# SensorPCB.net
KiCad netlist of a schematic drawn in EAGLE
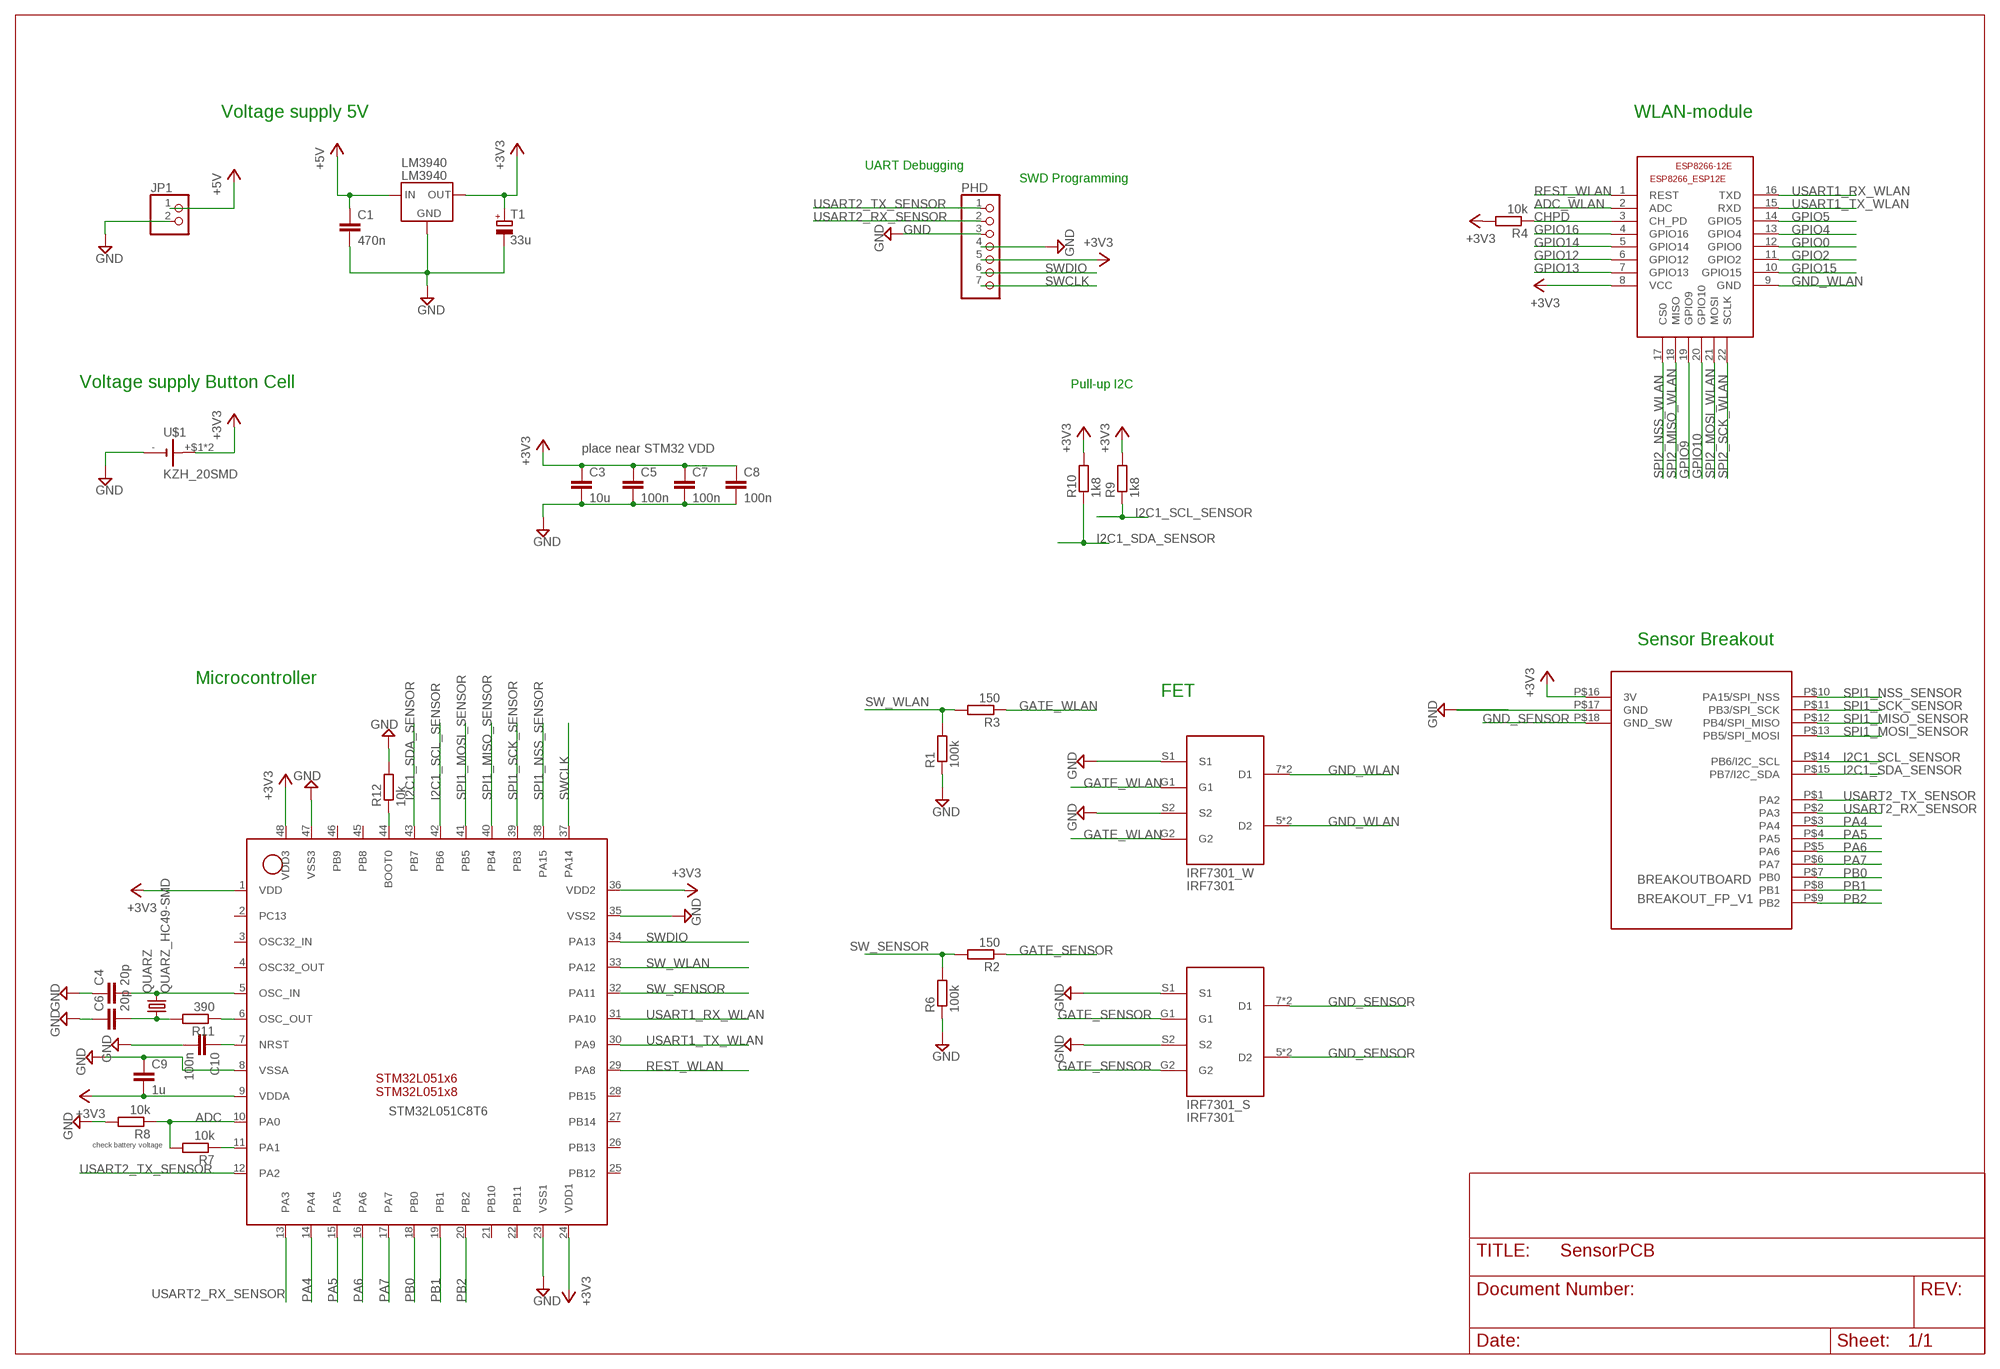
[diagram p0: schematic, sheet 1]

(export (version "E")
  (design (tool "Eeschema 10.0.6"))
  (components
    (comp (ref "BREAKOUTBOARD")
      (value "BREAKOUT_FP_V1")
      (footprint "eagle-import:BREAKOUT_FOOTPRINT_V1")
      (libsource (lib "eagle-import") (part "BREAKOUT_FP_V1"))
    )
    (comp (ref "C1")
      (value "470n")
      (footprint "eagle-import:C0805")
      (libsource (lib "eagle-import") (part "C-EUC0805"))
    )
    (comp (ref "C3")
      (value "10u")
      (footprint "eagle-import:C0805")
      (libsource (lib "eagle-import") (part "C-EUC0805"))
    )
    (comp (ref "C4")
      (value "20p")
      (footprint "eagle-import:C0805")
      (libsource (lib "eagle-import") (part "C-EUC0805"))
    )
    (comp (ref "C5")
      (value "100n")
      (footprint "eagle-import:C0805")
      (libsource (lib "eagle-import") (part "C-EUC0805"))
    )
    (comp (ref "C6")
      (value "20p")
      (footprint "eagle-import:C0805")
      (libsource (lib "eagle-import") (part "C-EUC0805"))
    )
    (comp (ref "C7")
      (value "100n")
      (footprint "eagle-import:C0805")
      (libsource (lib "eagle-import") (part "C-EUC0805"))
    )
    (comp (ref "C8")
      (value "100n")
      (footprint "eagle-import:C0805")
      (libsource (lib "eagle-import") (part "C-EUC0805"))
    )
    (comp (ref "C9")
      (value "1u")
      (footprint "eagle-import:C0805")
      (libsource (lib "eagle-import") (part "C-EUC0805"))
    )
    (comp (ref "C10")
      (value "100n")
      (footprint "eagle-import:C0805")
      (libsource (lib "eagle-import") (part "C-EUC0805"))
    )
    (comp (ref "ESP8266-12E")
      (value "ESP8266-12EESP8266-ESP12E")
      (footprint "eagle-import:ESP8266-ESP12E")
      (libsource (lib "eagle-import") (part "ESP8266-12EESP8266-ESP12E"))
    )
    (comp (ref "IRF7301_S")
      (value "IRF7301")
      (footprint "eagle-import:IRF7301_PACK_SO8")
      (libsource (lib "eagle-import") (part "IRF7301"))
    )
    (comp (ref "IRF7301_W")
      (value "IRF7301")
      (footprint "eagle-import:IRF7301_PACK_SO8")
      (libsource (lib "eagle-import") (part "IRF7301"))
    )
    (comp (ref "JP1")
      (value "PINHD-1X2_2.54-SMD")
      (footprint "eagle-import:1X02SMD")
      (libsource (lib "eagle-import") (part "PINHD-1X2_2.54-SMD"))
    )
    (comp (ref "LM3940")
      (value "LM3940")
      (footprint "eagle-import:LM3940_PACK")
      (libsource (lib "eagle-import") (part "LM3940"))
    )
    (comp (ref "PHD")
      (value "PINHD-1X7_2.54-SMD")
      (footprint "eagle-import:1X07SMD")
      (libsource (lib "eagle-import") (part "PINHD-1X7_2.54-SMD"))
    )
    (comp (ref "QUARZ")
      (value "QUARZ_HC49-SMD")
      (footprint "eagle-import:HC49-SMD")
      (libsource (lib "eagle-import") (part "QUARZ_HC49-SMD"))
    )
    (comp (ref "R1")
      (value "100k")
      (footprint "eagle-import:R0805")
      (libsource (lib "eagle-import") (part "R-EU_R0805"))
    )
    (comp (ref "R2")
      (value "150")
      (footprint "eagle-import:R0805")
      (libsource (lib "eagle-import") (part "R-EU_R0805"))
    )
    (comp (ref "R3")
      (value "150")
      (footprint "eagle-import:R0805")
      (libsource (lib "eagle-import") (part "R-EU_R0805"))
    )
    (comp (ref "R4")
      (value "10k")
      (footprint "eagle-import:R0805")
      (libsource (lib "eagle-import") (part "R-EU_R0805"))
    )
    (comp (ref "R6")
      (value "100k")
      (footprint "eagle-import:R0805")
      (libsource (lib "eagle-import") (part "R-EU_R0805"))
    )
    (comp (ref "R7")
      (value "10k")
      (footprint "eagle-import:R0805")
      (libsource (lib "eagle-import") (part "R-EU_R0805"))
    )
    (comp (ref "R8")
      (value "10k")
      (footprint "eagle-import:R0805")
      (libsource (lib "eagle-import") (part "R-EU_R0805"))
    )
    (comp (ref "R9")
      (value "1k8")
      (footprint "eagle-import:R0805")
      (libsource (lib "eagle-import") (part "R-EU_R0805"))
    )
    (comp (ref "R10")
      (value "1k8")
      (footprint "eagle-import:R0805")
      (libsource (lib "eagle-import") (part "R-EU_R0805"))
    )
    (comp (ref "R11")
      (value "390")
      (footprint "eagle-import:R0805")
      (libsource (lib "eagle-import") (part "R-EU_R0805"))
    )
    (comp (ref "R12")
      (value "10k")
      (footprint "eagle-import:R0805")
      (libsource (lib "eagle-import") (part "R-EU_R0805"))
    )
    (comp (ref "STM32L051C8T6")
      (value "STM32L051X6/8")
      (footprint "eagle-import:LQFP48")
      (libsource (lib "eagle-import") (part "STM32L051X6/8"))
    )
    (comp (ref "T1")
      (value "33u")
      (footprint "eagle-import:1206")
      (libsource (lib "eagle-import") (part "CAP_TANTAL_1206"))
    )
    (comp (ref "U$1")
      (value "KZH_20SMD")
      (footprint "eagle-import:KHZ_20SMD")
      (libsource (lib "eagle-import") (part "KZH_20SMD"))
    )
  )
  (nets
    (net (code "1") (name "+3V3") (class "Default")
      (node (ref "BREAKOUTBOARD") (pin "P$16") (pinfunction "3V_P$16") (pintype "bidirectional"))
      (node (ref "C3") (pin "1") (pinfunction "1_1") (pintype "passive"))
      (node (ref "C5") (pin "1") (pinfunction "1_1") (pintype "passive"))
      (node (ref "C7") (pin "1") (pinfunction "1_1") (pintype "passive"))
      (node (ref "C8") (pin "1") (pinfunction "1_1") (pintype "passive"))
      (node (ref "C9") (pin "2") (pinfunction "2_2") (pintype "passive"))
      (node (ref "ESP8266-12E") (pin "8") (pinfunction "VCC_8") (pintype "bidirectional"))
      (node (ref "LM3940") (pin "3") (pinfunction "OUT_3") (pintype "passive"))
      (node (ref "PHD") (pin "5") (pinfunction "5_5") (pintype "passive"))
      (node (ref "R10") (pin "2") (pinfunction "2_2") (pintype "passive"))
      (node (ref "R4") (pin "2") (pinfunction "2_2") (pintype "passive"))
      (node (ref "R9") (pin "2") (pinfunction "2_2") (pintype "passive"))
      (node (ref "STM32L051C8T6") (pin "1") (pinfunction "VDD_1") (pintype "bidirectional"))
      (node (ref "STM32L051C8T6") (pin "24") (pinfunction "VDD1_24") (pintype "bidirectional"))
      (node (ref "STM32L051C8T6") (pin "36") (pinfunction "VDD2_36") (pintype "bidirectional"))
      (node (ref "STM32L051C8T6") (pin "48") (pinfunction "VDD3_48") (pintype "bidirectional"))
      (node (ref "STM32L051C8T6") (pin "9") (pinfunction "VDDA_9") (pintype "input"))
      (node (ref "T1") (pin "1") (pinfunction "+_1") (pintype "passive"))
      (node (ref "U$1") (pin "+$1") (pinfunction "+_+$1") (pintype "passive"))
      (node (ref "U$1") (pin "+$2") (pinfunction "+_+$2") (pintype "passive"))
    )
    (net (code "2") (name "+5V") (class "Default")
      (node (ref "C1") (pin "1") (pinfunction "1_1") (pintype "passive"))
      (node (ref "JP1") (pin "1") (pinfunction "1_1") (pintype "passive"))
      (node (ref "LM3940") (pin "1") (pinfunction "IN_1") (pintype "input"))
    )
    (net (code "3") (name "/ADC") (class "Default")
      (node (ref "R7") (pin "2") (pinfunction "2_2") (pintype "passive"))
      (node (ref "R8") (pin "1") (pinfunction "1_1") (pintype "passive"))
      (node (ref "STM32L051C8T6") (pin "10") (pinfunction "PA0_10") (pintype "passive"))
    )
    (net (code "4") (name "/ADC_WLAN") (class "Default")
      (node (ref "ESP8266-12E") (pin "2") (pinfunction "ADC_2") (pintype "bidirectional"))
    )
    (net (code "5") (name "/CHPD") (class "Default")
      (node (ref "ESP8266-12E") (pin "3") (pinfunction "CH_PD_3") (pintype "bidirectional"))
      (node (ref "R4") (pin "1") (pinfunction "1_1") (pintype "passive"))
    )
    (net (code "6") (name "/GATE_SENSOR") (class "Default")
      (node (ref "IRF7301_S") (pin "G1") (pinfunction "G1_G1") (pintype "bidirectional"))
      (node (ref "IRF7301_S") (pin "G2") (pinfunction "G2_G2") (pintype "bidirectional"))
      (node (ref "R2") (pin "1") (pinfunction "1_1") (pintype "passive"))
    )
    (net (code "7") (name "/GATE_WLAN") (class "Default")
      (node (ref "IRF7301_W") (pin "G1") (pinfunction "G1_G1") (pintype "bidirectional"))
      (node (ref "IRF7301_W") (pin "G2") (pinfunction "G2_G2") (pintype "bidirectional"))
      (node (ref "R3") (pin "1") (pinfunction "1_1") (pintype "passive"))
    )
    (net (code "8") (name "/GND_SENSOR") (class "Default")
      (node (ref "BREAKOUTBOARD") (pin "P$18") (pinfunction "GND_SW_P$18") (pintype "bidirectional"))
      (node (ref "IRF7301_S") (pin "5") (pinfunction "D2_5") (pintype "bidirectional"))
      (node (ref "IRF7301_S") (pin "7") (pinfunction "D1_7") (pintype "bidirectional"))
      (node (ref "IRF7301_S") (pin "D1") (pinfunction "D1_D1") (pintype "bidirectional"))
      (node (ref "IRF7301_S") (pin "D2") (pinfunction "D2_D2") (pintype "bidirectional"))
    )
    (net (code "9") (name "/GND_WLAN") (class "Default")
      (node (ref "ESP8266-12E") (pin "9") (pinfunction "GND_9") (pintype "bidirectional"))
      (node (ref "IRF7301_W") (pin "5") (pinfunction "D2_5") (pintype "bidirectional"))
      (node (ref "IRF7301_W") (pin "7") (pinfunction "D1_7") (pintype "bidirectional"))
      (node (ref "IRF7301_W") (pin "D1") (pinfunction "D1_D1") (pintype "bidirectional"))
      (node (ref "IRF7301_W") (pin "D2") (pinfunction "D2_D2") (pintype "bidirectional"))
    )
    (net (code "10") (name "/GPIO0") (class "Default")
      (node (ref "ESP8266-12E") (pin "12") (pinfunction "GPIO0_12") (pintype "bidirectional"))
    )
    (net (code "11") (name "/GPIO2") (class "Default")
      (node (ref "ESP8266-12E") (pin "11") (pinfunction "GPIO2_11") (pintype "bidirectional"))
    )
    (net (code "12") (name "/GPIO4") (class "Default")
      (node (ref "ESP8266-12E") (pin "13") (pinfunction "GPIO4_13") (pintype "bidirectional"))
    )
    (net (code "13") (name "/GPIO5") (class "Default")
      (node (ref "ESP8266-12E") (pin "14") (pinfunction "GPIO5_14") (pintype "bidirectional"))
    )
    (net (code "14") (name "/GPIO9") (class "Default")
      (node (ref "ESP8266-12E") (pin "19") (pinfunction "GPIO9_19") (pintype "bidirectional"))
    )
    (net (code "15") (name "/GPIO10") (class "Default")
      (node (ref "ESP8266-12E") (pin "20") (pinfunction "GPIO10_20") (pintype "bidirectional"))
    )
    (net (code "16") (name "/GPIO12") (class "Default")
      (node (ref "ESP8266-12E") (pin "6") (pinfunction "GPIO12_6") (pintype "bidirectional"))
    )
    (net (code "17") (name "/GPIO13") (class "Default")
      (node (ref "ESP8266-12E") (pin "7") (pinfunction "GPIO13_7") (pintype "bidirectional"))
    )
    (net (code "18") (name "/GPIO14") (class "Default")
      (node (ref "ESP8266-12E") (pin "5") (pinfunction "GPIO14_5") (pintype "bidirectional"))
    )
    (net (code "19") (name "/GPIO15") (class "Default")
      (node (ref "ESP8266-12E") (pin "10") (pinfunction "GPIO15_10") (pintype "bidirectional"))
    )
    (net (code "20") (name "/GPIO16") (class "Default")
      (node (ref "ESP8266-12E") (pin "4") (pinfunction "GPIO16_4") (pintype "bidirectional"))
    )
    (net (code "21") (name "/I2C1_SCL_SENSOR") (class "Default")
      (node (ref "BREAKOUTBOARD") (pin "P$14") (pinfunction "PB6/I2C_SCL_P$14") (pintype "bidirectional"))
      (node (ref "R9") (pin "1") (pinfunction "1_1") (pintype "passive"))
      (node (ref "STM32L051C8T6") (pin "42") (pinfunction "PB6_42") (pintype "bidirectional"))
    )
    (net (code "22") (name "/I2C1_SDA_SENSOR") (class "Default")
      (node (ref "BREAKOUTBOARD") (pin "P$15") (pinfunction "PB7/I2C_SDA_P$15") (pintype "bidirectional"))
      (node (ref "R10") (pin "1") (pinfunction "1_1") (pintype "passive"))
      (node (ref "STM32L051C8T6") (pin "43") (pinfunction "PB7_43") (pintype "bidirectional"))
    )
    (net (code "23") (name "/PA4") (class "Default")
      (node (ref "BREAKOUTBOARD") (pin "P$3") (pinfunction "PA4_P$3") (pintype "bidirectional"))
      (node (ref "STM32L051C8T6") (pin "14") (pinfunction "PA4_14") (pintype "bidirectional"))
    )
    (net (code "24") (name "/PA5") (class "Default")
      (node (ref "BREAKOUTBOARD") (pin "P$4") (pinfunction "PA5_P$4") (pintype "bidirectional"))
      (node (ref "STM32L051C8T6") (pin "15") (pinfunction "PA5_15") (pintype "bidirectional"))
    )
    (net (code "25") (name "/PA6") (class "Default")
      (node (ref "BREAKOUTBOARD") (pin "P$5") (pinfunction "PA6_P$5") (pintype "bidirectional"))
      (node (ref "STM32L051C8T6") (pin "16") (pinfunction "PA6_16") (pintype "bidirectional"))
    )
    (net (code "26") (name "/PA7") (class "Default")
      (node (ref "BREAKOUTBOARD") (pin "P$6") (pinfunction "PA7_P$6") (pintype "bidirectional"))
      (node (ref "STM32L051C8T6") (pin "17") (pinfunction "PA7_17") (pintype "bidirectional"))
    )
    (net (code "27") (name "/PB0") (class "Default")
      (node (ref "BREAKOUTBOARD") (pin "P$7") (pinfunction "PB0_P$7") (pintype "bidirectional"))
      (node (ref "STM32L051C8T6") (pin "18") (pinfunction "PB0_18") (pintype "bidirectional"))
    )
    (net (code "28") (name "/PB1") (class "Default")
      (node (ref "BREAKOUTBOARD") (pin "P$8") (pinfunction "PB1_P$8") (pintype "bidirectional"))
      (node (ref "STM32L051C8T6") (pin "19") (pinfunction "PB1_19") (pintype "bidirectional"))
    )
    (net (code "29") (name "/PB2") (class "Default")
      (node (ref "BREAKOUTBOARD") (pin "P$9") (pinfunction "PB2_P$9") (pintype "bidirectional"))
      (node (ref "STM32L051C8T6") (pin "20") (pinfunction "PB2_20") (pintype "bidirectional"))
    )
    (net (code "30") (name "/REST_WLAN") (class "Default")
      (node (ref "ESP8266-12E") (pin "1") (pinfunction "REST_1") (pintype "bidirectional"))
      (node (ref "STM32L051C8T6") (pin "29") (pinfunction "PA8_29") (pintype "bidirectional"))
    )
    (net (code "31") (name "/SPI1_MISO_SENSOR") (class "Default")
      (node (ref "BREAKOUTBOARD") (pin "P$12") (pinfunction "PB4/SPI_MISO_P$12") (pintype "bidirectional"))
      (node (ref "STM32L051C8T6") (pin "40") (pinfunction "PB4_40") (pintype "bidirectional"))
    )
    (net (code "32") (name "/SPI1_MOSI_SENSOR") (class "Default")
      (node (ref "BREAKOUTBOARD") (pin "P$13") (pinfunction "PB5/SPI_MOSI_P$13") (pintype "bidirectional"))
      (node (ref "STM32L051C8T6") (pin "41") (pinfunction "PB5_41") (pintype "bidirectional"))
    )
    (net (code "33") (name "/SPI1_NSS_SENSOR") (class "Default")
      (node (ref "BREAKOUTBOARD") (pin "P$10") (pinfunction "PA15/SPI_NSS_P$10") (pintype "bidirectional"))
      (node (ref "STM32L051C8T6") (pin "38") (pinfunction "PA15_38") (pintype "bidirectional"))
    )
    (net (code "34") (name "/SPI1_SCK_SENSOR") (class "Default")
      (node (ref "BREAKOUTBOARD") (pin "P$11") (pinfunction "PB3/SPI_SCK_P$11") (pintype "bidirectional"))
      (node (ref "STM32L051C8T6") (pin "39") (pinfunction "PB3_39") (pintype "bidirectional"))
    )
    (net (code "35") (name "/SPI2_MISO_WLAN") (class "Default")
      (node (ref "ESP8266-12E") (pin "18") (pinfunction "MISO_18") (pintype "bidirectional"))
    )
    (net (code "36") (name "/SPI2_MOSI_WLAN") (class "Default")
      (node (ref "ESP8266-12E") (pin "21") (pinfunction "MOSI_21") (pintype "bidirectional"))
    )
    (net (code "37") (name "/SPI2_NSS_WLAN") (class "Default")
      (node (ref "ESP8266-12E") (pin "17") (pinfunction "CS0_17") (pintype "bidirectional"))
    )
    (net (code "38") (name "/SPI2_SCK_WLAN") (class "Default")
      (node (ref "ESP8266-12E") (pin "22") (pinfunction "SCLK_22") (pintype "bidirectional"))
    )
    (net (code "39") (name "/SWCLK") (class "Default")
      (node (ref "PHD") (pin "7") (pinfunction "7_7") (pintype "passive"))
      (node (ref "STM32L051C8T6") (pin "37") (pinfunction "PA14_37") (pintype "bidirectional"))
    )
    (net (code "40") (name "/SWDIO") (class "Default")
      (node (ref "PHD") (pin "6") (pinfunction "6_6") (pintype "passive"))
      (node (ref "STM32L051C8T6") (pin "34") (pinfunction "PA13_34") (pintype "bidirectional"))
    )
    (net (code "41") (name "/SW_SENSOR") (class "Default")
      (node (ref "R2") (pin "2") (pinfunction "2_2") (pintype "passive"))
      (node (ref "R6") (pin "2") (pinfunction "2_2") (pintype "passive"))
      (node (ref "STM32L051C8T6") (pin "32") (pinfunction "PA11_32") (pintype "bidirectional"))
    )
    (net (code "42") (name "/SW_WLAN") (class "Default")
      (node (ref "R1") (pin "2") (pinfunction "2_2") (pintype "passive"))
      (node (ref "R3") (pin "2") (pinfunction "2_2") (pintype "passive"))
      (node (ref "STM32L051C8T6") (pin "33") (pinfunction "PA12_33") (pintype "bidirectional"))
    )
    (net (code "43") (name "/USART1_RX_WLAN") (class "Default")
      (node (ref "ESP8266-12E") (pin "16") (pinfunction "TXD_16") (pintype "bidirectional"))
      (node (ref "STM32L051C8T6") (pin "31") (pinfunction "PA10_31") (pintype "bidirectional"))
    )
    (net (code "44") (name "/USART1_TX_WLAN") (class "Default")
      (node (ref "ESP8266-12E") (pin "15") (pinfunction "RXD_15") (pintype "bidirectional"))
      (node (ref "STM32L051C8T6") (pin "30") (pinfunction "PA9_30") (pintype "bidirectional"))
    )
    (net (code "45") (name "/USART2_RX_SENSOR") (class "Default")
      (node (ref "BREAKOUTBOARD") (pin "P$2") (pinfunction "PA3_P$2") (pintype "bidirectional"))
      (node (ref "PHD") (pin "2") (pinfunction "2_2") (pintype "passive"))
      (node (ref "STM32L051C8T6") (pin "13") (pinfunction "PA3_13") (pintype "bidirectional"))
    )
    (net (code "46") (name "/USART2_TX_SENSOR") (class "Default")
      (node (ref "BREAKOUTBOARD") (pin "P$1") (pinfunction "PA2_P$1") (pintype "bidirectional"))
      (node (ref "PHD") (pin "1") (pinfunction "1_1") (pintype "passive"))
      (node (ref "STM32L051C8T6") (pin "12") (pinfunction "PA2_12") (pintype "power_in"))
    )
    (net (code "47") (name "GND") (class "Default")
      (node (ref "BREAKOUTBOARD") (pin "P$17") (pinfunction "GND_P$17") (pintype "bidirectional"))
      (node (ref "C1") (pin "2") (pinfunction "2_2") (pintype "passive"))
      (node (ref "C10") (pin "2") (pinfunction "2_2") (pintype "passive"))
      (node (ref "C3") (pin "2") (pinfunction "2_2") (pintype "passive"))
      (node (ref "C4") (pin "1") (pinfunction "1_1") (pintype "passive"))
      (node (ref "C5") (pin "2") (pinfunction "2_2") (pintype "passive"))
      (node (ref "C6") (pin "1") (pinfunction "1_1") (pintype "passive"))
      (node (ref "C7") (pin "2") (pinfunction "2_2") (pintype "passive"))
      (node (ref "C8") (pin "2") (pinfunction "2_2") (pintype "passive"))
      (node (ref "C9") (pin "1") (pinfunction "1_1") (pintype "passive"))
      (node (ref "IRF7301_S") (pin "S1") (pinfunction "S1_S1") (pintype "bidirectional"))
      (node (ref "IRF7301_S") (pin "S2") (pinfunction "S2_S2") (pintype "bidirectional"))
      (node (ref "IRF7301_W") (pin "S1") (pinfunction "S1_S1") (pintype "bidirectional"))
      (node (ref "IRF7301_W") (pin "S2") (pinfunction "S2_S2") (pintype "bidirectional"))
      (node (ref "JP1") (pin "2") (pinfunction "2_2") (pintype "passive"))
      (node (ref "LM3940") (pin "2") (pinfunction "GND_2") (pintype "input"))
      (node (ref "LM3940") (pin "4") (pinfunction "GND_4") (pintype "input"))
      (node (ref "PHD") (pin "3") (pinfunction "3_3") (pintype "passive"))
      (node (ref "PHD") (pin "4") (pinfunction "4_4") (pintype "passive"))
      (node (ref "R1") (pin "1") (pinfunction "1_1") (pintype "passive"))
      (node (ref "R12") (pin "2") (pinfunction "2_2") (pintype "passive"))
      (node (ref "R6") (pin "1") (pinfunction "1_1") (pintype "passive"))
      (node (ref "R8") (pin "2") (pinfunction "2_2") (pintype "passive"))
      (node (ref "STM32L051C8T6") (pin "23") (pinfunction "VSS1_23") (pintype "bidirectional"))
      (node (ref "STM32L051C8T6") (pin "35") (pinfunction "VSS2_35") (pintype "bidirectional"))
      (node (ref "STM32L051C8T6") (pin "47") (pinfunction "VSS3_47") (pintype "bidirectional"))
      (node (ref "STM32L051C8T6") (pin "8") (pinfunction "VSSA_8") (pintype "input"))
      (node (ref "T1") (pin "2") (pinfunction "-_2") (pintype "passive"))
      (node (ref "U$1") (pin "-") (pinfunction "-_-") (pintype "passive"))
    )
    (net (code "48") (name "Net-(C6-Pad2)") (class "Default")
      (node (ref "C6") (pin "2") (pinfunction "2_2") (pintype "passive"))
      (node (ref "QUARZ") (pin "1") (pinfunction "1_1") (pintype "passive"))
      (node (ref "R11") (pin "2") (pinfunction "2_2") (pintype "passive"))
    )
    (net (code "49") (name "Net-(STM32L051C8T6-BOOT0)") (class "Default")
      (node (ref "R12") (pin "1") (pinfunction "1_1") (pintype "passive"))
      (node (ref "STM32L051C8T6") (pin "44") (pinfunction "BOOT0_44") (pintype "bidirectional"))
    )
    (net (code "50") (name "Net-(STM32L051C8T6-NRST)") (class "Default")
      (node (ref "C10") (pin "1") (pinfunction "1_1") (pintype "passive"))
      (node (ref "STM32L051C8T6") (pin "7") (pinfunction "NRST_7") (pintype "input"))
    )
    (net (code "51") (name "Net-(STM32L051C8T6-OSC_IN)") (class "Default")
      (node (ref "C4") (pin "2") (pinfunction "2_2") (pintype "passive"))
      (node (ref "QUARZ") (pin "2") (pinfunction "2_2") (pintype "passive"))
      (node (ref "STM32L051C8T6") (pin "5") (pinfunction "OSC_IN_5") (pintype "input"))
    )
    (net (code "52") (name "Net-(STM32L051C8T6-OSC_OUT)") (class "Default")
      (node (ref "R11") (pin "1") (pinfunction "1_1") (pintype "passive"))
      (node (ref "STM32L051C8T6") (pin "6") (pinfunction "OSC_OUT_6") (pintype "input"))
    )
    (net (code "53") (name "Net-(STM32L051C8T6-PA1)") (class "Default")
      (node (ref "R7") (pin "1") (pinfunction "1_1") (pintype "passive"))
      (node (ref "STM32L051C8T6") (pin "11") (pinfunction "PA1_11") (pintype "power_in"))
    )
    (net (code "54") (name "unconnected-(STM32L051C8T6-OSC32_IN-Pad3)") (class "Default")
      (node (ref "STM32L051C8T6") (pin "3") (pinfunction "OSC32_IN_3") (pintype "bidirectional"))
    )
    (net (code "55") (name "unconnected-(STM32L051C8T6-OSC32_OUT-Pad4)") (class "Default")
      (node (ref "STM32L051C8T6") (pin "4") (pinfunction "OSC32_OUT_4") (pintype "input"))
    )
    (net (code "56") (name "unconnected-(STM32L051C8T6-PB8-Pad45)") (class "Default")
      (node (ref "STM32L051C8T6") (pin "45") (pinfunction "PB8_45") (pintype "bidirectional"))
    )
    (net (code "57") (name "unconnected-(STM32L051C8T6-PB9-Pad46)") (class "Default")
      (node (ref "STM32L051C8T6") (pin "46") (pinfunction "PB9_46") (pintype "bidirectional"))
    )
    (net (code "58") (name "unconnected-(STM32L051C8T6-PB10-Pad21)") (class "Default")
      (node (ref "STM32L051C8T6") (pin "21") (pinfunction "PB10_21") (pintype "bidirectional"))
    )
    (net (code "59") (name "unconnected-(STM32L051C8T6-PB11-Pad22)") (class "Default")
      (node (ref "STM32L051C8T6") (pin "22") (pinfunction "PB11_22") (pintype "bidirectional"))
    )
    (net (code "60") (name "unconnected-(STM32L051C8T6-PB12-Pad25)") (class "Default")
      (node (ref "STM32L051C8T6") (pin "25") (pinfunction "PB12_25") (pintype "bidirectional"))
    )
    (net (code "61") (name "unconnected-(STM32L051C8T6-PB13-Pad26)") (class "Default")
      (node (ref "STM32L051C8T6") (pin "26") (pinfunction "PB13_26") (pintype "bidirectional"))
    )
    (net (code "62") (name "unconnected-(STM32L051C8T6-PB14-Pad27)") (class "Default")
      (node (ref "STM32L051C8T6") (pin "27") (pinfunction "PB14_27") (pintype "bidirectional"))
    )
    (net (code "63") (name "unconnected-(STM32L051C8T6-PB15-Pad28)") (class "Default")
      (node (ref "STM32L051C8T6") (pin "28") (pinfunction "PB15_28") (pintype "bidirectional"))
    )
    (net (code "64") (name "unconnected-(STM32L051C8T6-PC13-Pad2)") (class "Default")
      (node (ref "STM32L051C8T6") (pin "2") (pinfunction "PC13_2") (pintype "bidirectional"))
    )
  )
)
